# ServoIface_v1_0.net
KiCad netlist of a schematic drawn in EAGLE
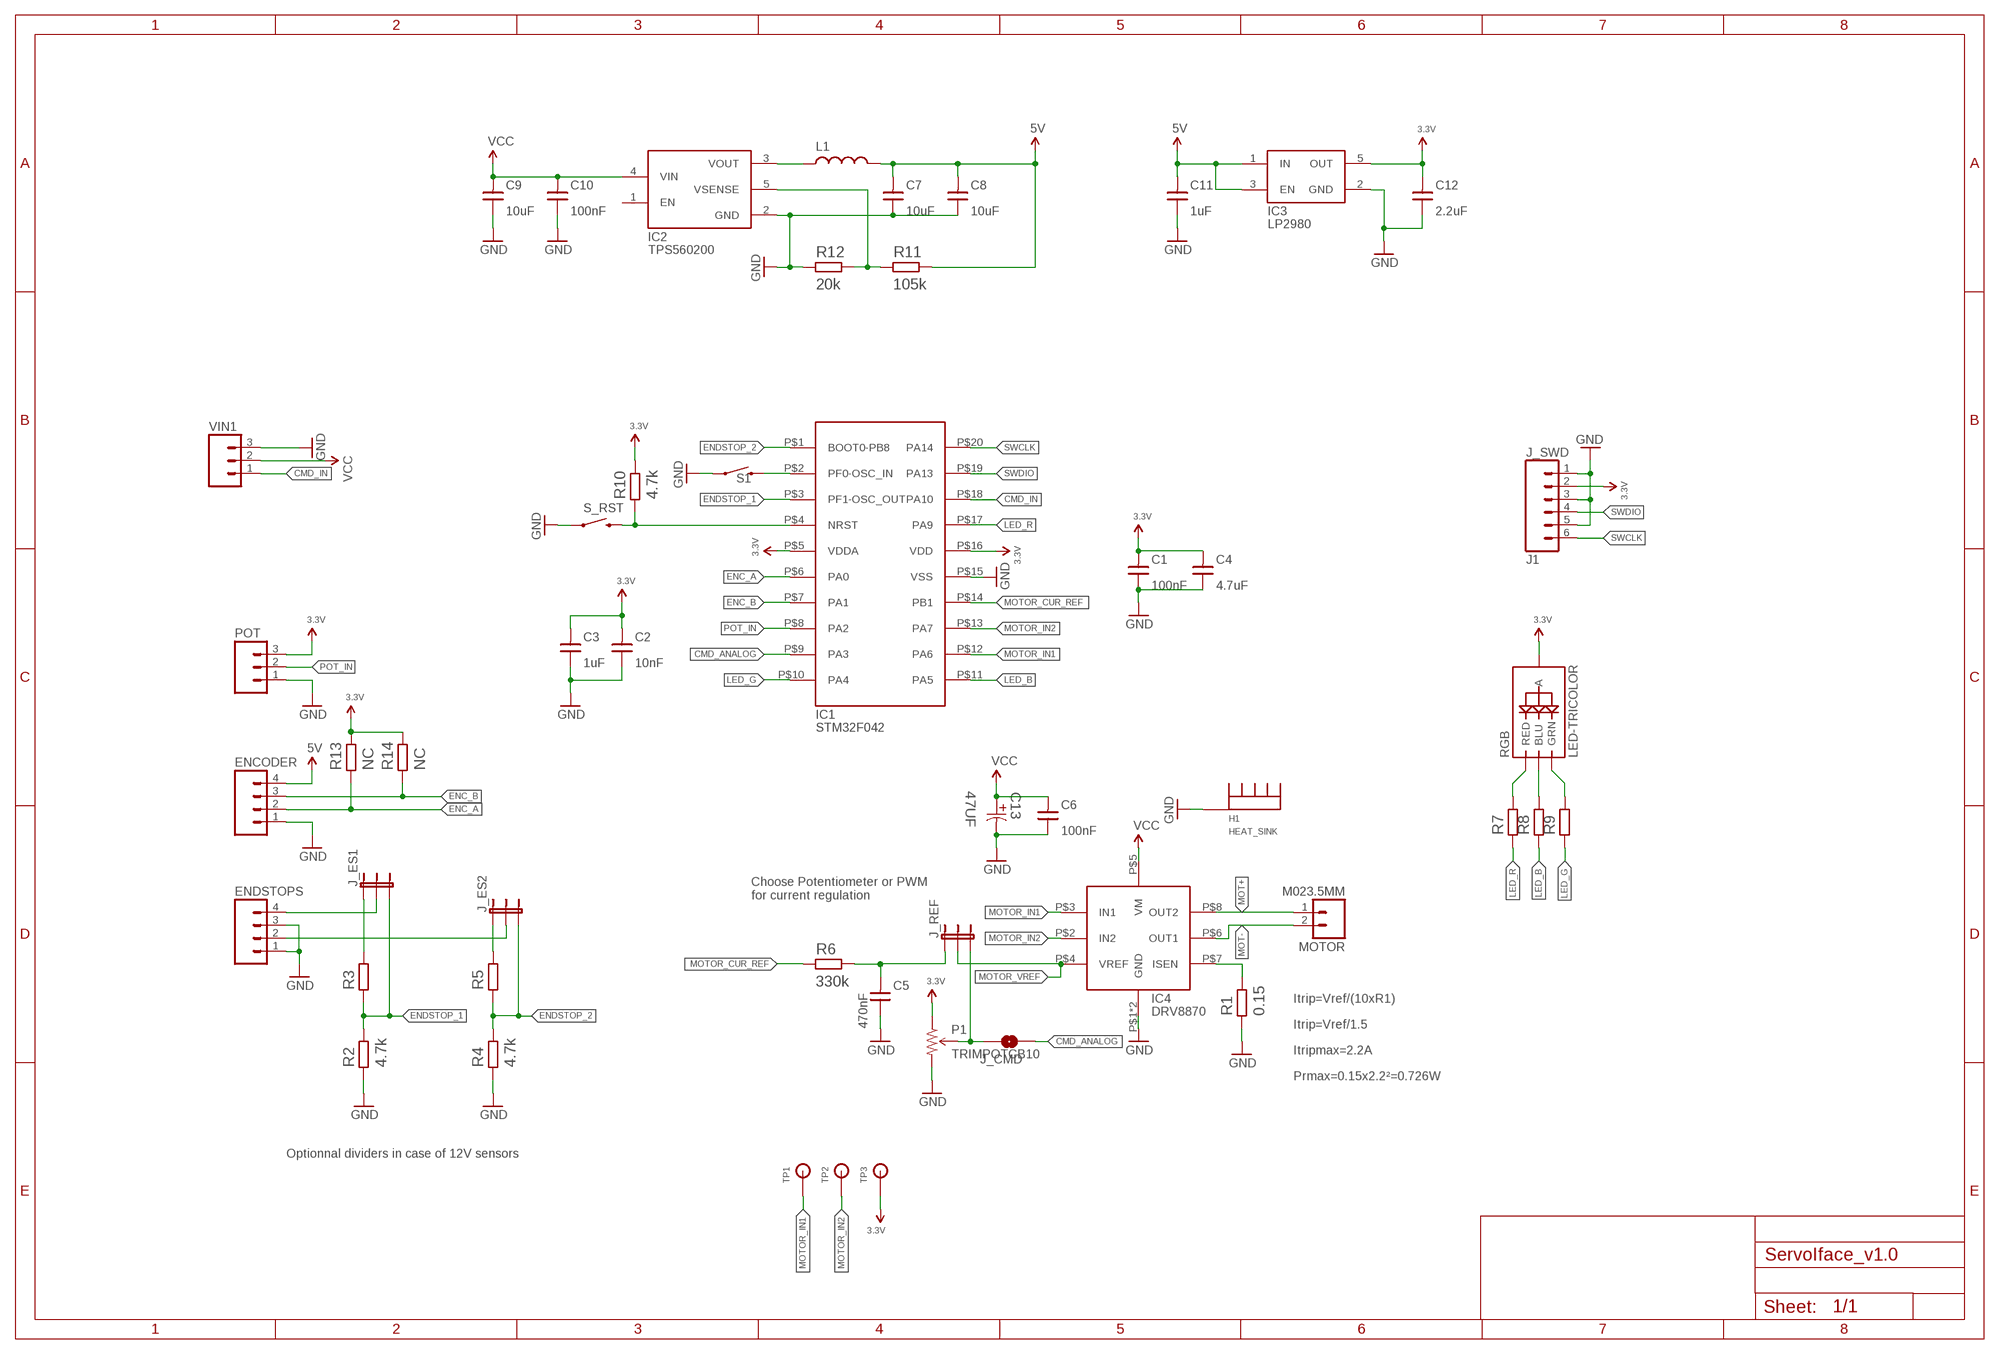
[diagram p0: schematic, sheet 1]

(export (version "E")
  (design (tool "Eeschema 10.0.6"))
  (components
    (comp (ref "C1")
      (value "100nF")
      (footprint "eagle-import:R0603")
      (libsource (lib "eagle-import") (part "C0603"))
    )
    (comp (ref "C2")
      (value "10nF")
      (footprint "eagle-import:R0603")
      (libsource (lib "eagle-import") (part "C0603"))
    )
    (comp (ref "C3")
      (value "1uF")
      (footprint "eagle-import:R0805")
      (libsource (lib "eagle-import") (part "C0805"))
    )
    (comp (ref "C4")
      (value "4.7uF")
      (footprint "eagle-import:R0805")
      (libsource (lib "eagle-import") (part "C0805"))
    )
    (comp (ref "C5")
      (value "470nF")
      (footprint "eagle-import:R0603")
      (libsource (lib "eagle-import") (part "C0603"))
    )
    (comp (ref "C6")
      (value "100nF")
      (footprint "eagle-import:R0603")
      (libsource (lib "eagle-import") (part "C0603"))
    )
    (comp (ref "C7")
      (value "10uF")
      (footprint "eagle-import:R0805")
      (libsource (lib "eagle-import") (part "C0805"))
    )
    (comp (ref "C8")
      (value "10uF")
      (footprint "eagle-import:R0805")
      (libsource (lib "eagle-import") (part "C0805"))
    )
    (comp (ref "C9")
      (value "10uF")
      (footprint "eagle-import:1206")
      (libsource (lib "eagle-import") (part "C1206"))
    )
    (comp (ref "C10")
      (value "100nF")
      (footprint "eagle-import:R0603")
      (libsource (lib "eagle-import") (part "C0603"))
    )
    (comp (ref "C11")
      (value "1uF")
      (footprint "eagle-import:R0805")
      (libsource (lib "eagle-import") (part "C0805"))
    )
    (comp (ref "C12")
      (value "2.2uF")
      (footprint "eagle-import:R0805")
      (libsource (lib "eagle-import") (part "C0805"))
    )
    (comp (ref "C13")
      (value "47UF")
      (footprint "eagle-import:CAPPR200-500X1600")
      (fields (field (name "MPN") "EEUFM1E470") (field (name "TOLERANCE") "±20 %"))
      (libsource (lib "eagle-import") (part "C_PANA-P2.0FM1E470"))
    )
    (comp (ref "ENCODER")
      (value "M04SCREW")
      (footprint "eagle-import:SCREWTERMINAL-3.5MM-4")
      (libsource (lib "eagle-import") (part "M04SCREW"))
    )
    (comp (ref "ENDSTOPS")
      (value "M04SCREW")
      (footprint "eagle-import:SCREWTERMINAL-3.5MM-4")
      (libsource (lib "eagle-import") (part "M04SCREW"))
    )
    (comp (ref "H1")
      (value "HEAT_SINK")
      (footprint "eagle-import:HEAT_A5_SA")
      (libsource (lib "eagle-import") (part "HEAT_SINK"))
    )
    (comp (ref "IC1")
      (value "STM32F042")
      (footprint "eagle-import:TSSOP20")
      (libsource (lib "eagle-import") (part "STM32F042"))
    )
    (comp (ref "IC2")
      (value "TPS560200")
      (footprint "eagle-import:SOT23-5L")
      (libsource (lib "eagle-import") (part "TPS560200"))
    )
    (comp (ref "IC3")
      (value "LP2980")
      (footprint "eagle-import:SOT23-5L")
      (libsource (lib "eagle-import") (part "LP2980"))
    )
    (comp (ref "IC4")
      (value "DRV8870")
      (footprint "eagle-import:HSOP_8P")
      (libsource (lib "eagle-import") (part "DRV8870"))
    )
    (comp (ref "J1")
      (value "J_SWD")
      (footprint "eagle-import:ZIF-06-1MM")
      (libsource (lib "eagle-import") (part "ZIF-06-1MM"))
    )
    (comp (ref "J_CMD")
      (value "JUMPER-PAD-2-NO")
      (footprint "eagle-import:PAD-JUMPER-2-NO_NO_SILK")
      (libsource (lib "eagle-import") (part "JUMPER-PAD-2-NO"))
    )
    (comp (ref "J_ES1")
      (value "JUMPER-3SMD")
      (footprint "eagle-import:SJ_3")
      (libsource (lib "eagle-import") (part "JUMPER-3SMD"))
    )
    (comp (ref "J_ES2")
      (value "JUMPER-3SMD")
      (footprint "eagle-import:SJ_3")
      (libsource (lib "eagle-import") (part "JUMPER-3SMD"))
    )
    (comp (ref "J_REF")
      (value "JUMPER-3SMD")
      (footprint "eagle-import:SJ_3")
      (libsource (lib "eagle-import") (part "JUMPER-3SMD"))
    )
    (comp (ref "L1")
      (value "LNRG_4026")
      (footprint "eagle-import:NRG_4026")
      (libsource (lib "eagle-import") (part "LNRG_4026"))
    )
    (comp (ref "MOTOR")
      (value "M023.5MM")
      (footprint "eagle-import:SCREWTERMINAL-3.5MM-2")
      (libsource (lib "eagle-import") (part "M023.5MM"))
    )
    (comp (ref "P1")
      (value "TRIMPOTCB10")
      (footprint "eagle-import:POT_CB10")
      (libsource (lib "eagle-import") (part "TRIMPOTCB10"))
    )
    (comp (ref "POT")
      (value "M03SCREW")
      (footprint "eagle-import:SCREWTERMINAL-3.5MM-3")
      (libsource (lib "eagle-import") (part "M03SCREW"))
    )
    (comp (ref "R1")
      (value "0.15")
      (footprint "eagle-import:CRF2512")
      (libsource (lib "eagle-import") (part "R2512"))
    )
    (comp (ref "R2")
      (value "4.7k")
      (footprint "eagle-import:R0603")
      (libsource (lib "eagle-import") (part "R0603"))
    )
    (comp (ref "R3")
      (value "R0603")
      (footprint "eagle-import:R0603")
      (libsource (lib "eagle-import") (part "R0603"))
    )
    (comp (ref "R4")
      (value "4.7k")
      (footprint "eagle-import:R0603")
      (libsource (lib "eagle-import") (part "R0603"))
    )
    (comp (ref "R5")
      (value "R0603")
      (footprint "eagle-import:R0603")
      (libsource (lib "eagle-import") (part "R0603"))
    )
    (comp (ref "R6")
      (value "330k")
      (footprint "eagle-import:R0603")
      (libsource (lib "eagle-import") (part "R0603"))
    )
    (comp (ref "R7")
      (value "R0603")
      (footprint "eagle-import:R0603")
      (libsource (lib "eagle-import") (part "R0603"))
    )
    (comp (ref "R8")
      (value "R0603")
      (footprint "eagle-import:R0603")
      (libsource (lib "eagle-import") (part "R0603"))
    )
    (comp (ref "R9")
      (value "R0603")
      (footprint "eagle-import:R0603")
      (libsource (lib "eagle-import") (part "R0603"))
    )
    (comp (ref "R10")
      (value "4.7k")
      (footprint "eagle-import:R0603")
      (libsource (lib "eagle-import") (part "R0603"))
    )
    (comp (ref "R11")
      (value "105k")
      (footprint "eagle-import:R0603")
      (libsource (lib "eagle-import") (part "R0603"))
    )
    (comp (ref "R12")
      (value "20k")
      (footprint "eagle-import:R0603")
      (libsource (lib "eagle-import") (part "R0603"))
    )
    (comp (ref "R13")
      (value "NC")
      (footprint "eagle-import:R0603")
      (libsource (lib "eagle-import") (part "R0603"))
    )
    (comp (ref "R14")
      (value "NC")
      (footprint "eagle-import:R0603")
      (libsource (lib "eagle-import") (part "R0603"))
    )
    (comp (ref "RGB")
      (value "LED-TRICOLOR")
      (footprint "eagle-import:PLCC4")
      (libsource (lib "eagle-import") (part "LED-TRICOLOR"))
    )
    (comp (ref "S1")
      (value "SWITCH-MOMENTARY-2SMD-3")
      (footprint "eagle-import:TACTILE_SWITCH_SMD-3")
      (libsource (lib "eagle-import") (part "SWITCH-MOMENTARY-2SMD-3"))
    )
    (comp (ref "S_RST")
      (value "SWITCH-MOMENTARY-2SMD-3")
      (footprint "eagle-import:TACTILE_SWITCH_SMD-3")
      (libsource (lib "eagle-import") (part "SWITCH-MOMENTARY-2SMD-3"))
    )
    (comp (ref "TP1")
      (value "TEST_POINT_R04")
      (footprint "eagle-import:TP_R04")
      (libsource (lib "eagle-import") (part "TEST_POINT_R04"))
    )
    (comp (ref "TP2")
      (value "TEST_POINT_R04")
      (footprint "eagle-import:TP_R04")
      (libsource (lib "eagle-import") (part "TEST_POINT_R04"))
    )
    (comp (ref "TP3")
      (value "TEST_POINT_R04")
      (footprint "eagle-import:TP_R04")
      (libsource (lib "eagle-import") (part "TEST_POINT_R04"))
    )
    (comp (ref "VIN1")
      (value "M03SCREW")
      (footprint "eagle-import:SCREWTERMINAL-3.5MM-3")
      (libsource (lib "eagle-import") (part "M03SCREW"))
    )
  )
  (nets
    (net (code "1") (name "3.3V") (class "Default")
      (node (ref "C1") (pin "2") (pinfunction "2_2") (pintype "bidirectional"))
      (node (ref "C12") (pin "2") (pinfunction "2_2") (pintype "bidirectional"))
      (node (ref "C2") (pin "2") (pinfunction "2_2") (pintype "bidirectional"))
      (node (ref "C3") (pin "2") (pinfunction "2_2") (pintype "bidirectional"))
      (node (ref "C4") (pin "2") (pinfunction "2_2") (pintype "bidirectional"))
      (node (ref "IC1") (pin "P$16") (pinfunction "VDD_P$16") (pintype "bidirectional"))
      (node (ref "IC1") (pin "P$5") (pinfunction "VDDA_P$5") (pintype "bidirectional"))
      (node (ref "IC3") (pin "5") (pinfunction "OUT_5") (pintype "bidirectional"))
      (node (ref "J1") (pin "2") (pinfunction "2_2") (pintype "passive"))
      (node (ref "P1") (pin "P$1") (pinfunction "CCW_P$1") (pintype "passive"))
      (node (ref "POT") (pin "3") (pinfunction "3_3") (pintype "passive"))
      (node (ref "R10") (pin "2") (pinfunction "2_2") (pintype "bidirectional"))
      (node (ref "R13") (pin "2") (pinfunction "2_2") (pintype "bidirectional"))
      (node (ref "R14") (pin "2") (pinfunction "2_2") (pintype "bidirectional"))
      (node (ref "RGB") (pin "P$1") (pinfunction "A_P$1") (pintype "bidirectional"))
      (node (ref "TP3") (pin "P$1") (pinfunction "P$1_P$1") (pintype "bidirectional"))
    )
    (net (code "2") (name "5V") (class "Default")
      (node (ref "C11") (pin "2") (pinfunction "2_2") (pintype "bidirectional"))
      (node (ref "C7") (pin "2") (pinfunction "2_2") (pintype "bidirectional"))
      (node (ref "C8") (pin "2") (pinfunction "2_2") (pintype "bidirectional"))
      (node (ref "ENCODER") (pin "4") (pinfunction "4_4") (pintype "passive"))
      (node (ref "IC3") (pin "1") (pinfunction "IN_1") (pintype "bidirectional"))
      (node (ref "IC3") (pin "3") (pinfunction "EN_3") (pintype "bidirectional"))
      (node (ref "L1") (pin "P$2") (pinfunction "2_P$2") (pintype "bidirectional"))
      (node (ref "R11") (pin "2") (pinfunction "2_2") (pintype "bidirectional"))
    )
    (net (code "3") (name "CMD_ANALOG") (class "Default")
      (node (ref "IC1") (pin "P$9") (pinfunction "PA3_P$9") (pintype "bidirectional"))
      (node (ref "J_CMD") (pin "1") (pinfunction "1_1") (pintype "passive"))
    )
    (net (code "4") (name "CMD_IN") (class "Default")
      (node (ref "IC1") (pin "P$18") (pinfunction "PA10_P$18") (pintype "bidirectional"))
      (node (ref "VIN1") (pin "1") (pinfunction "1_1") (pintype "passive"))
    )
    (net (code "5") (name "ENC_A") (class "Default")
      (node (ref "ENCODER") (pin "2") (pinfunction "2_2") (pintype "passive"))
      (node (ref "IC1") (pin "P$6") (pinfunction "PA0_P$6") (pintype "bidirectional"))
      (node (ref "R13") (pin "1") (pinfunction "1_1") (pintype "bidirectional"))
    )
    (net (code "6") (name "ENC_B") (class "Default")
      (node (ref "ENCODER") (pin "3") (pinfunction "3_3") (pintype "passive"))
      (node (ref "IC1") (pin "P$7") (pinfunction "PA1_P$7") (pintype "bidirectional"))
      (node (ref "R14") (pin "1") (pinfunction "1_1") (pintype "bidirectional"))
    )
    (net (code "7") (name "ENDSTOP_1") (class "Default")
      (node (ref "IC1") (pin "P$3") (pinfunction "PF1-OSC_OUT_P$3") (pintype "bidirectional"))
      (node (ref "J_ES1") (pin "3") (pinfunction "3_3") (pintype "passive"))
      (node (ref "R2") (pin "2") (pinfunction "2_2") (pintype "bidirectional"))
      (node (ref "R3") (pin "1") (pinfunction "1_1") (pintype "bidirectional"))
    )
    (net (code "8") (name "ENDSTOP_2") (class "Default")
      (node (ref "IC1") (pin "P$1") (pinfunction "BOOT0-PB8_P$1") (pintype "bidirectional"))
      (node (ref "J_ES2") (pin "3") (pinfunction "3_3") (pintype "passive"))
      (node (ref "R4") (pin "2") (pinfunction "2_2") (pintype "bidirectional"))
      (node (ref "R5") (pin "1") (pinfunction "1_1") (pintype "bidirectional"))
    )
    (net (code "9") (name "GND") (class "Default")
      (node (ref "C1") (pin "1") (pinfunction "1_1") (pintype "bidirectional"))
      (node (ref "C10") (pin "1") (pinfunction "1_1") (pintype "bidirectional"))
      (node (ref "C11") (pin "1") (pinfunction "1_1") (pintype "bidirectional"))
      (node (ref "C12") (pin "1") (pinfunction "1_1") (pintype "bidirectional"))
      (node (ref "C13") (pin "2") (pinfunction "2_2") (pintype "passive"))
      (node (ref "C2") (pin "1") (pinfunction "1_1") (pintype "bidirectional"))
      (node (ref "C3") (pin "1") (pinfunction "1_1") (pintype "bidirectional"))
      (node (ref "C4") (pin "1") (pinfunction "1_1") (pintype "bidirectional"))
      (node (ref "C5") (pin "1") (pinfunction "1_1") (pintype "bidirectional"))
      (node (ref "C6") (pin "1") (pinfunction "1_1") (pintype "bidirectional"))
      (node (ref "C7") (pin "1") (pinfunction "1_1") (pintype "bidirectional"))
      (node (ref "C8") (pin "1") (pinfunction "1_1") (pintype "bidirectional"))
      (node (ref "C9") (pin "1") (pinfunction "1_1") (pintype "bidirectional"))
      (node (ref "ENCODER") (pin "1") (pinfunction "1_1") (pintype "passive"))
      (node (ref "ENDSTOPS") (pin "1") (pinfunction "1_1") (pintype "passive"))
      (node (ref "ENDSTOPS") (pin "3") (pinfunction "3_3") (pintype "passive"))
      (node (ref "H1") (pin "P$1") (pinfunction "P$1_P$1") (pintype "bidirectional"))
      (node (ref "IC1") (pin "P$15") (pinfunction "VSS_P$15") (pintype "bidirectional"))
      (node (ref "IC2") (pin "2") (pinfunction "GND_2") (pintype "bidirectional"))
      (node (ref "IC3") (pin "2") (pinfunction "GND_2") (pintype "bidirectional"))
      (node (ref "IC4") (pin "P$1") (pinfunction "GND_P$1") (pintype "bidirectional"))
      (node (ref "IC4") (pin "PAD") (pinfunction "GND_PAD") (pintype "bidirectional"))
      (node (ref "J1") (pin "1") (pinfunction "1_1") (pintype "passive"))
      (node (ref "J1") (pin "3") (pinfunction "3_3") (pintype "passive"))
      (node (ref "J1") (pin "5") (pinfunction "5_5") (pintype "passive"))
      (node (ref "P1") (pin "P$2") (pinfunction "CW_P$2") (pintype "passive"))
      (node (ref "POT") (pin "1") (pinfunction "1_1") (pintype "passive"))
      (node (ref "R1") (pin "P$1") (pinfunction "1_P$1") (pintype "bidirectional"))
      (node (ref "R12") (pin "1") (pinfunction "1_1") (pintype "bidirectional"))
      (node (ref "R2") (pin "1") (pinfunction "1_1") (pintype "bidirectional"))
      (node (ref "R4") (pin "1") (pinfunction "1_1") (pintype "bidirectional"))
      (node (ref "S1") (pin "1") (pinfunction "1_1") (pintype "passive"))
      (node (ref "S_RST") (pin "1") (pinfunction "1_1") (pintype "passive"))
      (node (ref "VIN1") (pin "3") (pinfunction "3_3") (pintype "passive"))
    )
    (net (code "10") (name "LED_B") (class "Default")
      (node (ref "IC1") (pin "P$11") (pinfunction "PA5_P$11") (pintype "bidirectional"))
      (node (ref "R8") (pin "1") (pinfunction "1_1") (pintype "bidirectional"))
    )
    (net (code "11") (name "LED_G") (class "Default")
      (node (ref "IC1") (pin "P$10") (pinfunction "PA4_P$10") (pintype "bidirectional"))
      (node (ref "R9") (pin "1") (pinfunction "1_1") (pintype "bidirectional"))
    )
    (net (code "12") (name "LED_R") (class "Default")
      (node (ref "IC1") (pin "P$17") (pinfunction "PA9_P$17") (pintype "bidirectional"))
      (node (ref "R7") (pin "1") (pinfunction "1_1") (pintype "bidirectional"))
    )
    (net (code "13") (name "MOT+") (class "Default")
      (node (ref "IC4") (pin "P$8") (pinfunction "OUT2_P$8") (pintype "bidirectional"))
      (node (ref "MOTOR") (pin "1") (pinfunction "1_1") (pintype "passive"))
    )
    (net (code "14") (name "MOT-") (class "Default")
      (node (ref "IC4") (pin "P$6") (pinfunction "OUT1_P$6") (pintype "bidirectional"))
      (node (ref "MOTOR") (pin "2") (pinfunction "2_2") (pintype "passive"))
    )
    (net (code "15") (name "MOTOR_CUR_REF") (class "Default")
      (node (ref "IC1") (pin "P$14") (pinfunction "PB1_P$14") (pintype "bidirectional"))
      (node (ref "R6") (pin "1") (pinfunction "1_1") (pintype "bidirectional"))
    )
    (net (code "16") (name "MOTOR_IN1") (class "Default")
      (node (ref "IC1") (pin "P$12") (pinfunction "PA6_P$12") (pintype "bidirectional"))
      (node (ref "IC4") (pin "P$3") (pinfunction "IN1_P$3") (pintype "bidirectional"))
      (node (ref "TP1") (pin "P$1") (pinfunction "P$1_P$1") (pintype "bidirectional"))
    )
    (net (code "17") (name "MOTOR_IN2") (class "Default")
      (node (ref "IC1") (pin "P$13") (pinfunction "PA7_P$13") (pintype "bidirectional"))
      (node (ref "IC4") (pin "P$2") (pinfunction "IN2_P$2") (pintype "bidirectional"))
      (node (ref "TP2") (pin "P$1") (pinfunction "P$1_P$1") (pintype "bidirectional"))
    )
    (net (code "18") (name "MOTOR_VREF") (class "Default")
      (node (ref "IC4") (pin "P$4") (pinfunction "VREF_P$4") (pintype "bidirectional"))
      (node (ref "J_REF") (pin "2") (pinfunction "2_2") (pintype "passive"))
    )
    (net (code "19") (name "Net-(C5-Pad2)") (class "Default")
      (node (ref "C5") (pin "2") (pinfunction "2_2") (pintype "bidirectional"))
      (node (ref "J_REF") (pin "1") (pinfunction "1_1") (pintype "passive"))
      (node (ref "R6") (pin "2") (pinfunction "2_2") (pintype "bidirectional"))
    )
    (net (code "20") (name "Net-(ENDSTOPS-Pad2)") (class "Default")
      (node (ref "ENDSTOPS") (pin "2") (pinfunction "2_2") (pintype "passive"))
      (node (ref "J_ES2") (pin "2") (pinfunction "2_2") (pintype "passive"))
    )
    (net (code "21") (name "Net-(ENDSTOPS-Pad4)") (class "Default")
      (node (ref "ENDSTOPS") (pin "4") (pinfunction "4_4") (pintype "passive"))
      (node (ref "J_ES1") (pin "2") (pinfunction "2_2") (pintype "passive"))
    )
    (net (code "22") (name "Net-(IC1-NRST)") (class "Default")
      (node (ref "IC1") (pin "P$4") (pinfunction "NRST_P$4") (pintype "bidirectional"))
      (node (ref "R10") (pin "1") (pinfunction "1_1") (pintype "bidirectional"))
      (node (ref "S_RST") (pin "4") (pinfunction "2_4") (pintype "passive"))
    )
    (net (code "23") (name "Net-(IC1-PF0-OSC_IN)") (class "Default")
      (node (ref "IC1") (pin "P$2") (pinfunction "PF0-OSC_IN_P$2") (pintype "bidirectional"))
      (node (ref "S1") (pin "4") (pinfunction "2_4") (pintype "passive"))
    )
    (net (code "24") (name "Net-(IC2-VOUT)") (class "Default")
      (node (ref "IC2") (pin "3") (pinfunction "VOUT_3") (pintype "bidirectional"))
      (node (ref "L1") (pin "P$1") (pinfunction "1_P$1") (pintype "bidirectional"))
    )
    (net (code "25") (name "Net-(IC2-VSENSE)") (class "Default")
      (node (ref "IC2") (pin "5") (pinfunction "VSENSE_5") (pintype "bidirectional"))
      (node (ref "R11") (pin "1") (pinfunction "1_1") (pintype "bidirectional"))
      (node (ref "R12") (pin "2") (pinfunction "2_2") (pintype "bidirectional"))
    )
    (net (code "26") (name "Net-(IC4-ISEN)") (class "Default")
      (node (ref "IC4") (pin "P$7") (pinfunction "ISEN_P$7") (pintype "bidirectional"))
      (node (ref "R1") (pin "P$2") (pinfunction "2_P$2") (pintype "bidirectional"))
    )
    (net (code "27") (name "Net-(J_ES1-Pad1)") (class "Default")
      (node (ref "J_ES1") (pin "1") (pinfunction "1_1") (pintype "passive"))
      (node (ref "R3") (pin "2") (pinfunction "2_2") (pintype "bidirectional"))
    )
    (net (code "28") (name "Net-(J_ES2-Pad1)") (class "Default")
      (node (ref "J_ES2") (pin "1") (pinfunction "1_1") (pintype "passive"))
      (node (ref "R5") (pin "2") (pinfunction "2_2") (pintype "bidirectional"))
    )
    (net (code "29") (name "Net-(P1-WIPER)") (class "Default")
      (node (ref "J_CMD") (pin "2") (pinfunction "2_2") (pintype "passive"))
      (node (ref "J_REF") (pin "3") (pinfunction "3_3") (pintype "passive"))
      (node (ref "P1") (pin "P$3") (pinfunction "WIPER_P$3") (pintype "passive"))
    )
    (net (code "30") (name "Net-(RGB-BLU)") (class "Default")
      (node (ref "R8") (pin "2") (pinfunction "2_2") (pintype "bidirectional"))
      (node (ref "RGB") (pin "P$2") (pinfunction "BLU_P$2") (pintype "bidirectional"))
    )
    (net (code "31") (name "Net-(RGB-GRN)") (class "Default")
      (node (ref "R9") (pin "2") (pinfunction "2_2") (pintype "bidirectional"))
      (node (ref "RGB") (pin "P$3") (pinfunction "GRN_P$3") (pintype "bidirectional"))
    )
    (net (code "32") (name "Net-(RGB-RED)") (class "Default")
      (node (ref "R7") (pin "2") (pinfunction "2_2") (pintype "bidirectional"))
      (node (ref "RGB") (pin "P$4") (pinfunction "RED_P$4") (pintype "bidirectional"))
    )
    (net (code "33") (name "POT_IN") (class "Default")
      (node (ref "IC1") (pin "P$8") (pinfunction "PA2_P$8") (pintype "bidirectional"))
      (node (ref "POT") (pin "2") (pinfunction "2_2") (pintype "passive"))
    )
    (net (code "34") (name "SWCLK") (class "Default")
      (node (ref "IC1") (pin "P$20") (pinfunction "PA14_P$20") (pintype "bidirectional"))
      (node (ref "J1") (pin "6") (pinfunction "6_6") (pintype "passive"))
    )
    (net (code "35") (name "SWDIO") (class "Default")
      (node (ref "IC1") (pin "P$19") (pinfunction "PA13_P$19") (pintype "bidirectional"))
      (node (ref "J1") (pin "4") (pinfunction "4_4") (pintype "passive"))
    )
    (net (code "36") (name "VCC") (class "Default")
      (node (ref "C10") (pin "2") (pinfunction "2_2") (pintype "bidirectional"))
      (node (ref "C13") (pin "1") (pinfunction "1_1") (pintype "passive"))
      (node (ref "C6") (pin "2") (pinfunction "2_2") (pintype "bidirectional"))
      (node (ref "C9") (pin "2") (pinfunction "2_2") (pintype "bidirectional"))
      (node (ref "IC2") (pin "4") (pinfunction "VIN_4") (pintype "bidirectional"))
      (node (ref "IC4") (pin "P$5") (pinfunction "VM_P$5") (pintype "bidirectional"))
      (node (ref "VIN1") (pin "2") (pinfunction "2_2") (pintype "passive"))
    )
    (net (code "37") (name "unconnected-(IC2-EN-Pad1)") (class "Default")
      (node (ref "IC2") (pin "1") (pinfunction "EN_1") (pintype "bidirectional"))
    )
  )
)
